# ENERGIS_DispBrd_Rack-PDU_1_1_0.net
KiCad netlist of a schematic drawn in EAGLE
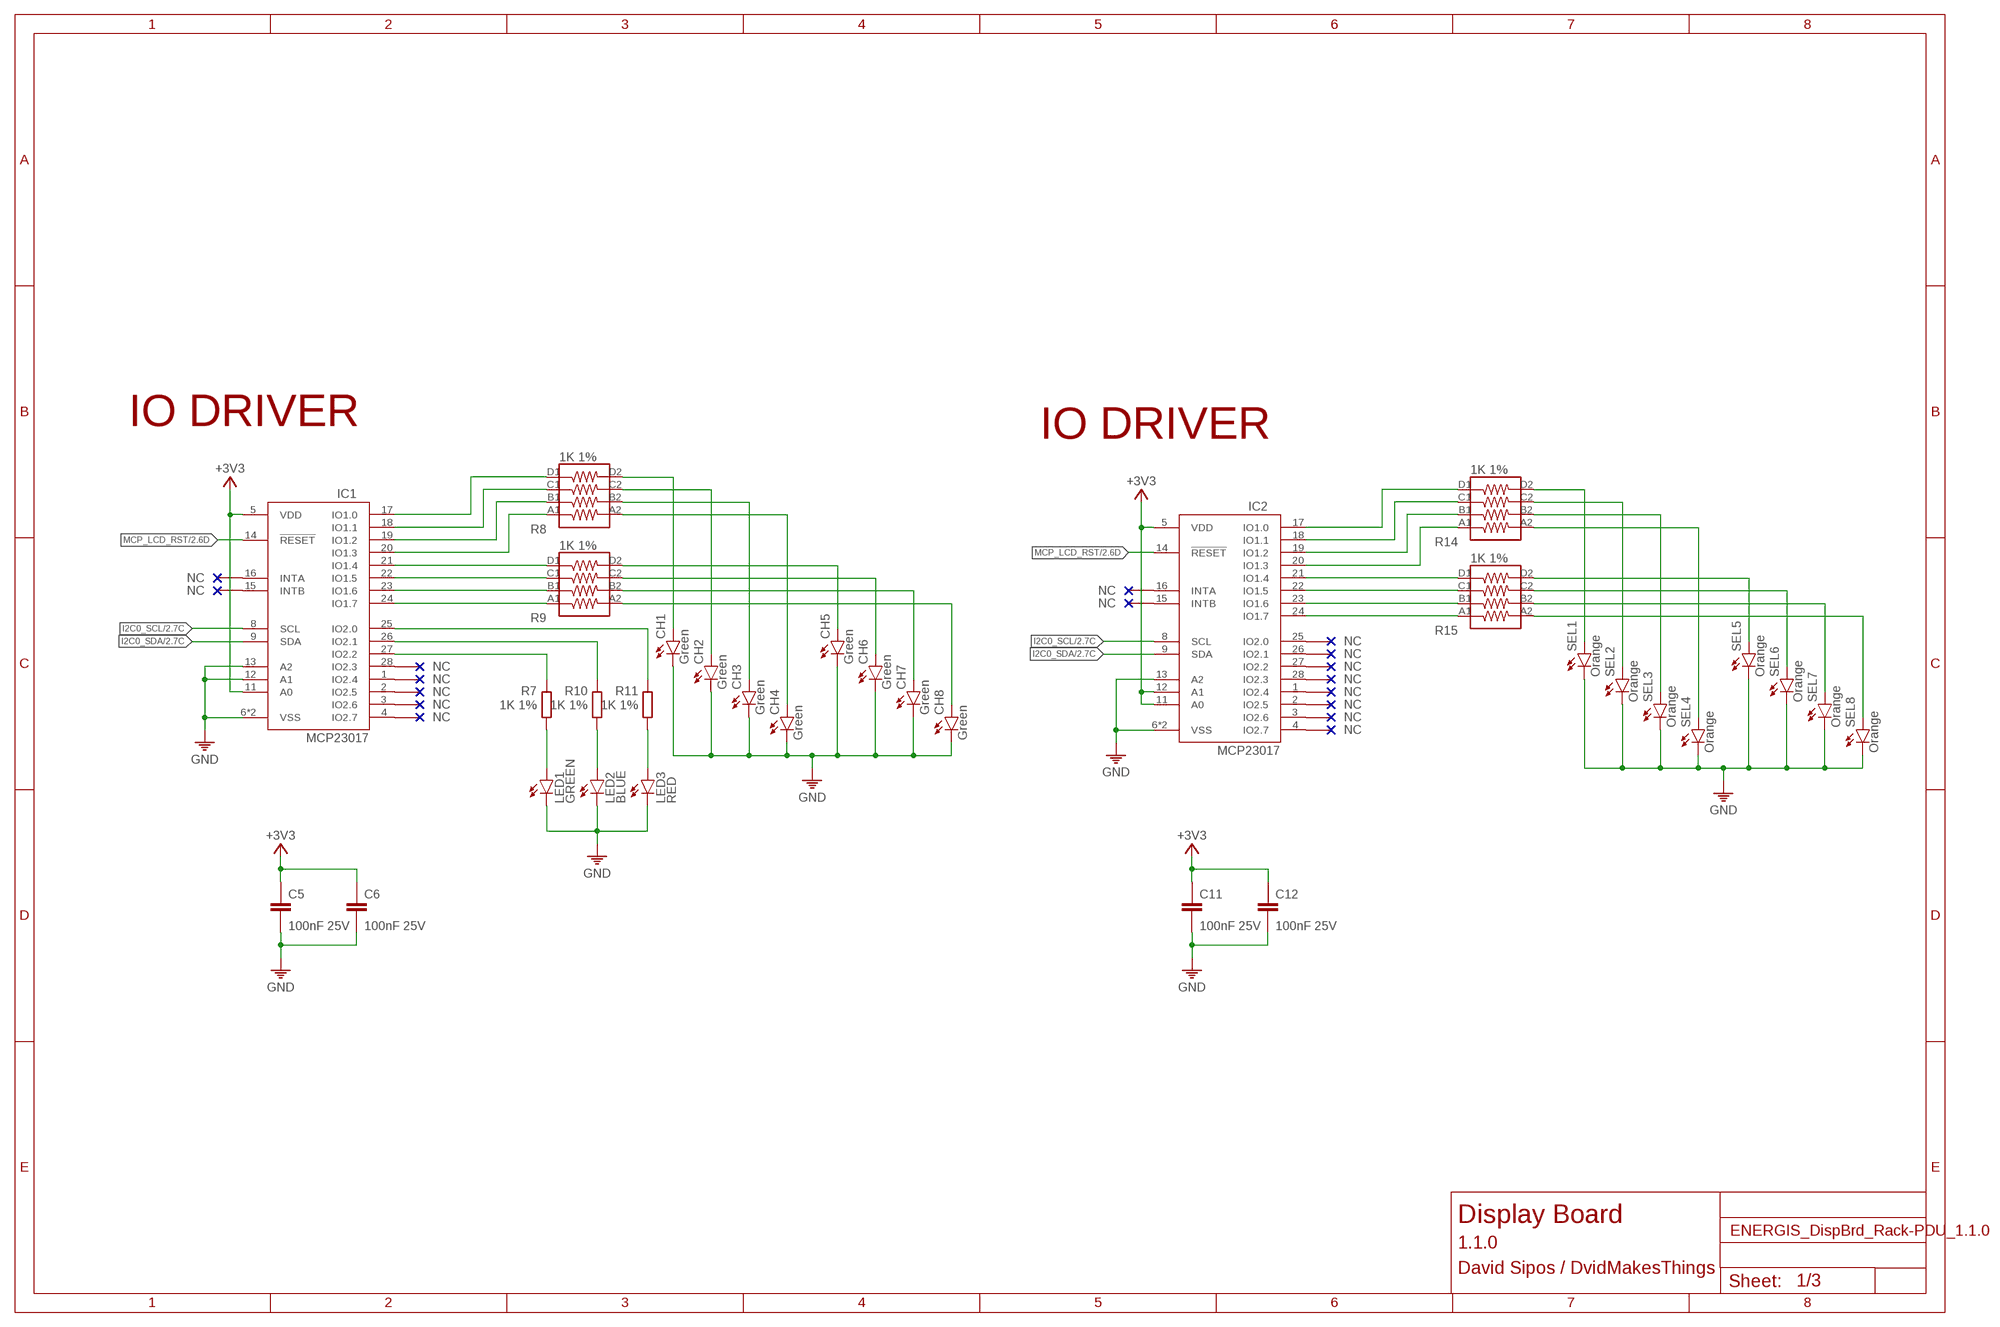
[diagram p0: schematic, sheet 1]
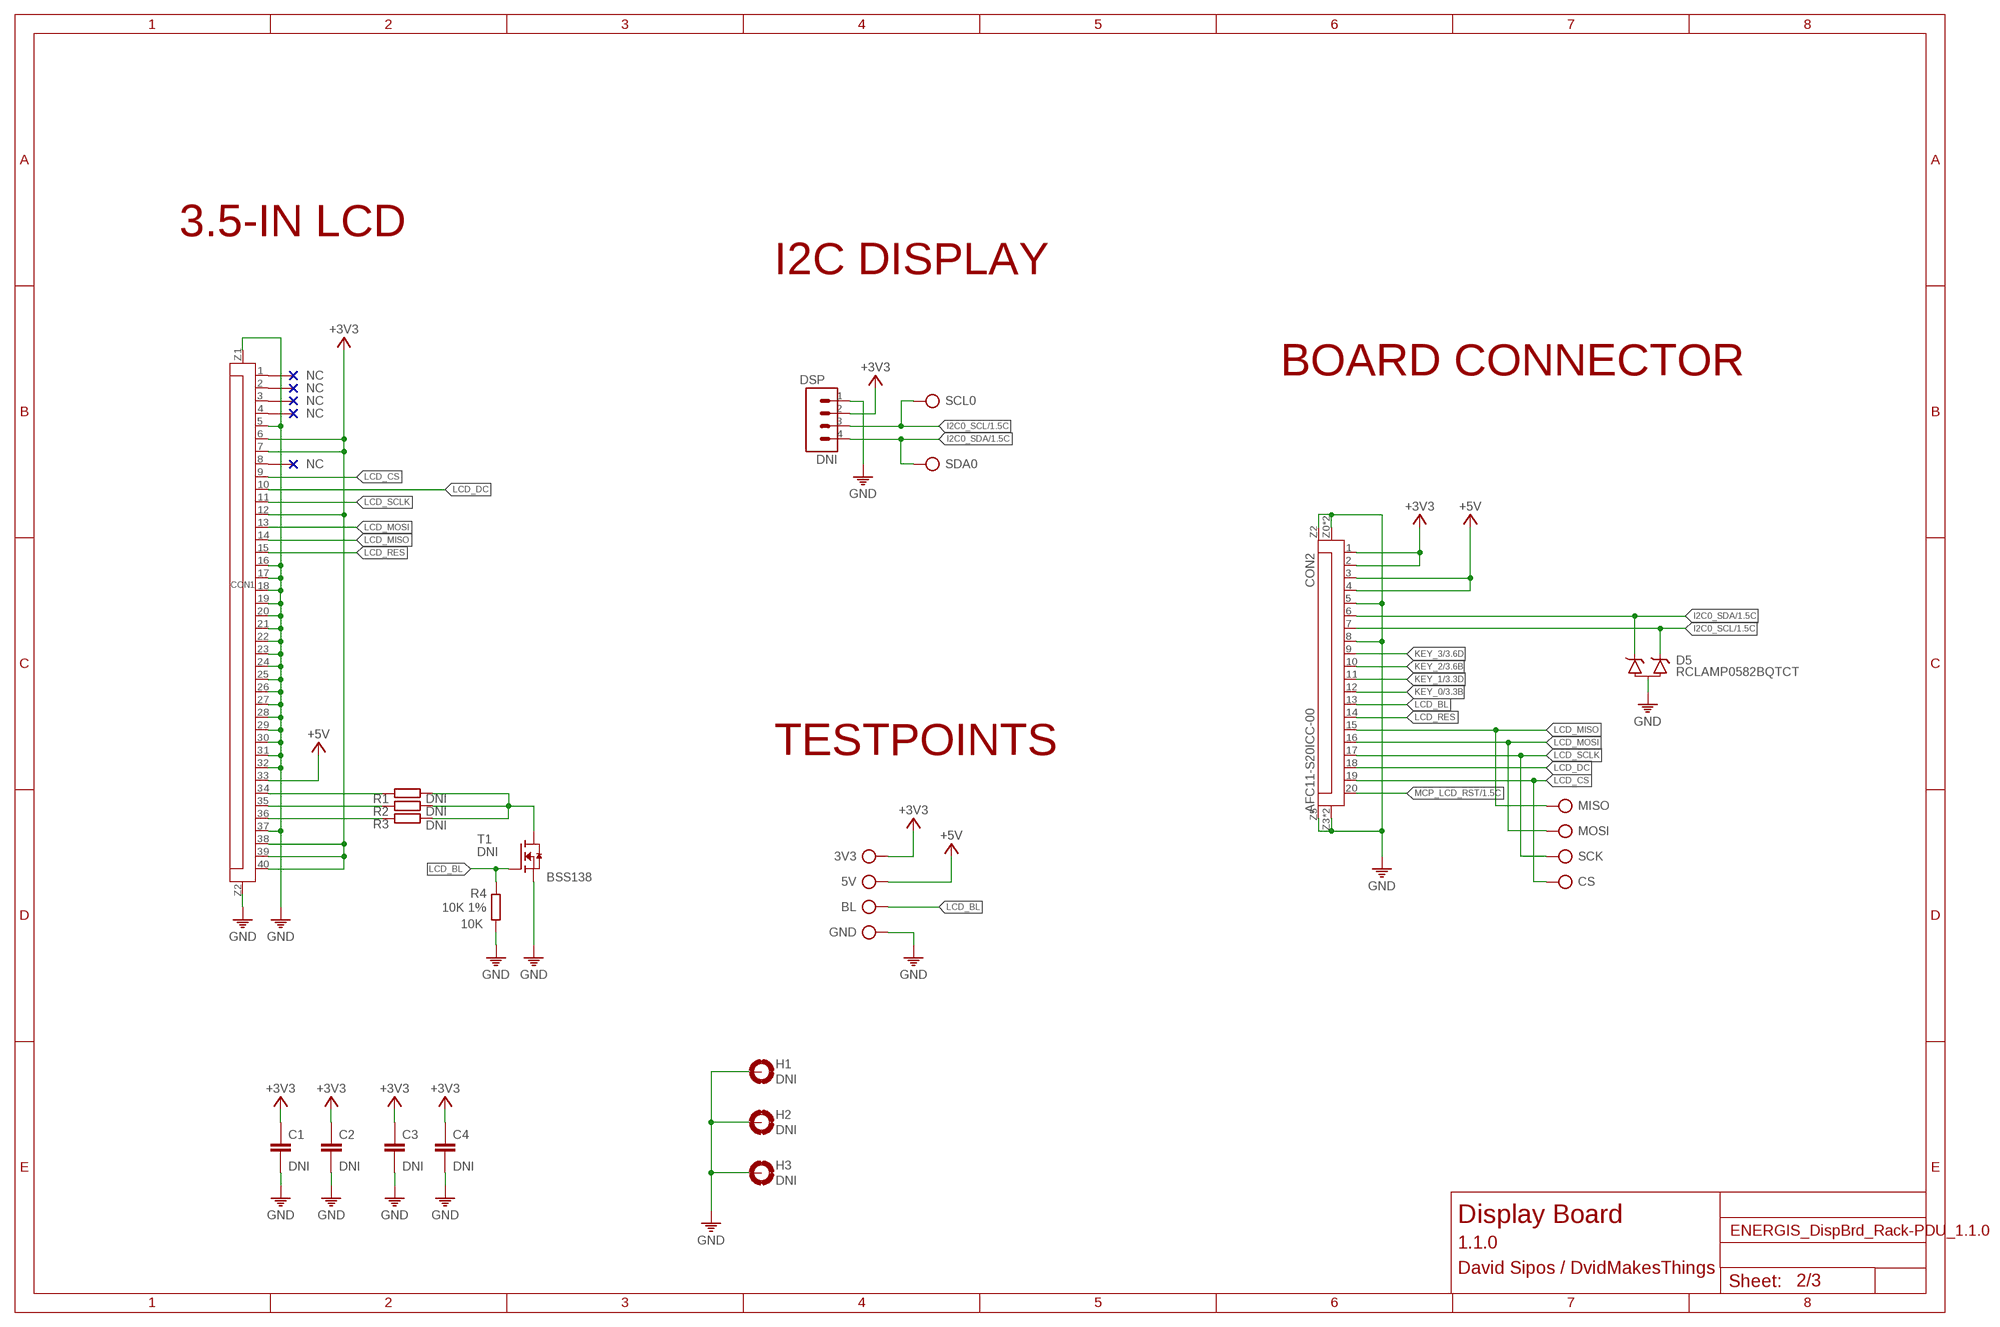
[diagram p1: schematic, sheet 2]
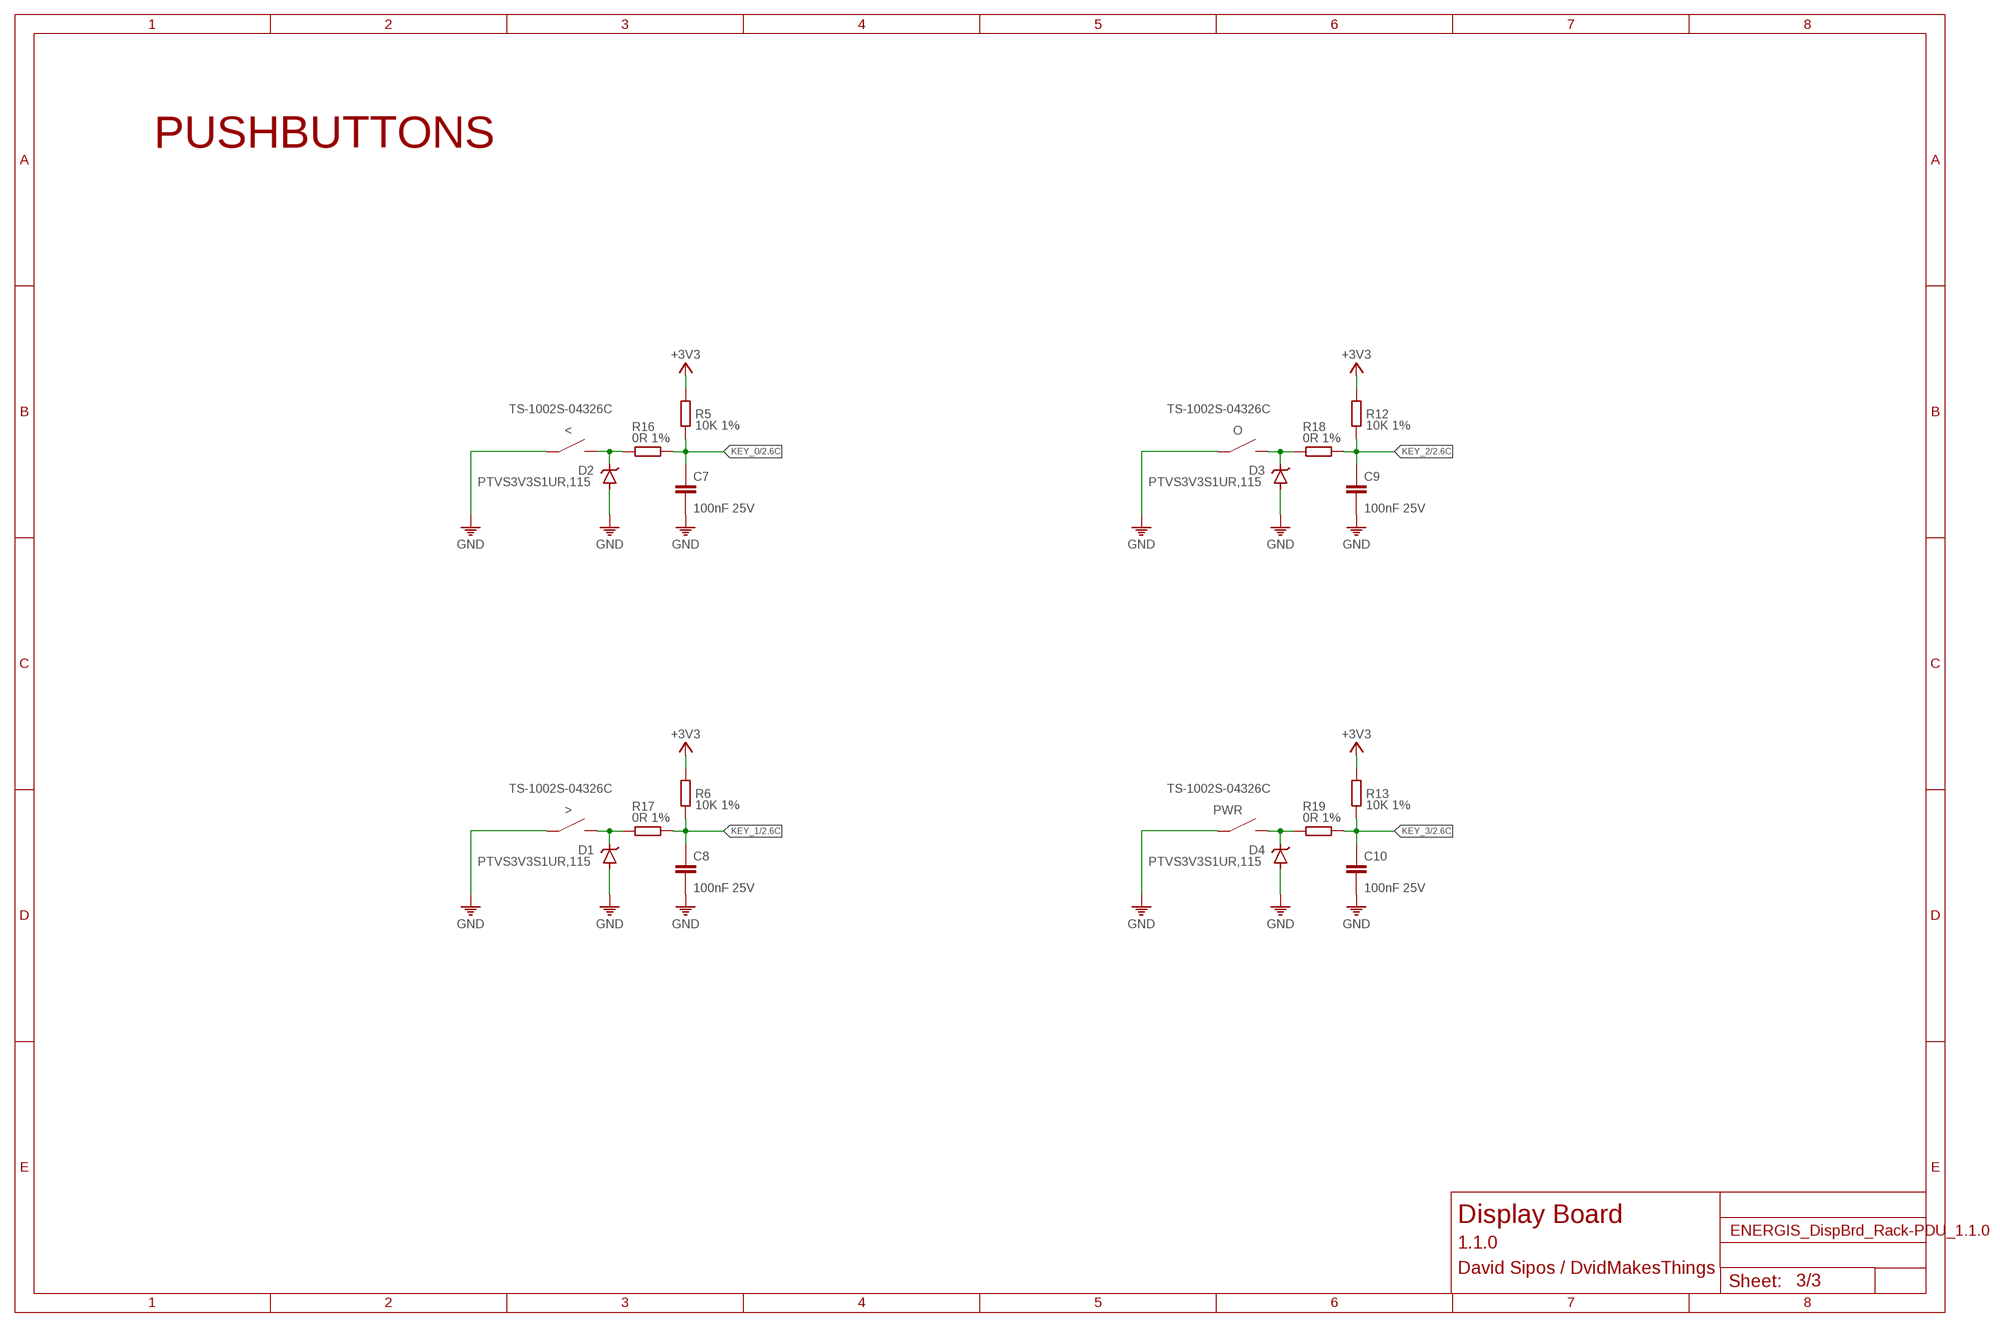
[diagram p2: schematic, sheet 3]

(export (version "E")
  (design (tool "Eeschema 10.0.6"))
  (components
    (comp (ref "<")
      (value "TS-1002S-04326C")
      (footprint "eagle-import:PUSHBUTTON-6X6")
      (fields
        (field (name "HQ_PART") "SW0049370")
        (field (name "LCSC_PART") "C455108")
        (field (name "MANUFACTURER") "USAKRO")
      )
      (libsource (lib "eagle-import") (part "SWITCH6X6-SHORT"))
    )
    (comp (ref ">")
      (value "TS-1002S-04326C")
      (footprint "eagle-import:PUSHBUTTON-6X6")
      (fields
        (field (name "HQ_PART") "SW0049370")
        (field (name "LCSC_PART") "C455108")
        (field (name "MANUFACTURER") "USAKRO")
      )
      (libsource (lib "eagle-import") (part "SWITCH6X6-SHORT"))
    )
    (comp (ref "C7")
      (value "100nF 25V")
      (footprint "eagle-import:0402")
      (fields
        (field (name "HQ_PART") "CA0176807")
        (field (name "LCSC_PART") "C56392")
        (field (name "MANUFACTURER") "Walsin")
      )
      (libsource (lib "eagle-import") (part "100NF-25V-0402"))
    )
    (comp (ref "C8")
      (value "100nF 25V")
      (footprint "eagle-import:0402")
      (fields
        (field (name "HQ_PART") "CA0176807")
        (field (name "LCSC_PART") "C56392")
        (field (name "MANUFACTURER") "Walsin")
      )
      (libsource (lib "eagle-import") (part "100NF-25V-0402"))
    )
    (comp (ref "C9")
      (value "100nF 25V")
      (footprint "eagle-import:0402")
      (fields
        (field (name "HQ_PART") "CA0176807")
        (field (name "LCSC_PART") "C56392")
        (field (name "MANUFACTURER") "Walsin")
      )
      (libsource (lib "eagle-import") (part "100NF-25V-0402"))
    )
    (comp (ref "C10")
      (value "100nF 25V")
      (footprint "eagle-import:0402")
      (fields
        (field (name "HQ_PART") "CA0176807")
        (field (name "LCSC_PART") "C56392")
        (field (name "MANUFACTURER") "Walsin")
      )
      (libsource (lib "eagle-import") (part "100NF-25V-0402"))
    )
    (comp (ref "D1")
      (value "PTVS3V3S1UR,115")
      (footprint "eagle-import:SOD-123")
      (fields
        (field (name "HQ_PART") "CP0009318")
        (field (name "LCSC_PART") "C183521")
        (field (name "MANUFACTURER") "Nexperia")
      )
      (libsource (lib "eagle-import") (part "PTVS3V3S1UR,115"))
    )
    (comp (ref "D2")
      (value "PTVS3V3S1UR,115")
      (footprint "eagle-import:SOD-123")
      (fields
        (field (name "HQ_PART") "CP0009318")
        (field (name "LCSC_PART") "C183521")
        (field (name "MANUFACTURER") "Nexperia")
      )
      (libsource (lib "eagle-import") (part "PTVS3V3S1UR,115"))
    )
    (comp (ref "D3")
      (value "PTVS3V3S1UR,115")
      (footprint "eagle-import:SOD-123")
      (fields
        (field (name "HQ_PART") "CP0009318")
        (field (name "LCSC_PART") "C183521")
        (field (name "MANUFACTURER") "Nexperia")
      )
      (libsource (lib "eagle-import") (part "PTVS3V3S1UR,115"))
    )
    (comp (ref "D4")
      (value "PTVS3V3S1UR,115")
      (footprint "eagle-import:SOD-123")
      (fields
        (field (name "HQ_PART") "CP0009318")
        (field (name "LCSC_PART") "C183521")
        (field (name "MANUFACTURER") "Nexperia")
      )
      (libsource (lib "eagle-import") (part "PTVS3V3S1UR,115"))
    )
    (comp (ref "O")
      (value "TS-1002S-04326C")
      (footprint "eagle-import:PUSHBUTTON-6X6")
      (fields
        (field (name "HQ_PART") "SW0049370")
        (field (name "LCSC_PART") "C455108")
        (field (name "MANUFACTURER") "USAKRO")
      )
      (libsource (lib "eagle-import") (part "SWITCH6X6-SHORT"))
    )
    (comp (ref "PWR")
      (value "TS-1002S-04326C")
      (footprint "eagle-import:PUSHBUTTON-6X6")
      (fields
        (field (name "HQ_PART") "SW0049370")
        (field (name "LCSC_PART") "C455108")
        (field (name "MANUFACTURER") "USAKRO")
      )
      (libsource (lib "eagle-import") (part "SWITCH6X6-SHORT"))
    )
    (comp (ref "R5")
      (value "10K 1%")
      (footprint "eagle-import:0402")
      (fields
        (field (name "HQ_PART") "RE0207399")
        (field (name "LCSC_PART") "C25744")
        (field (name "MANUFACTURER") "ROHM")
      )
      (libsource (lib "eagle-import") (part "10K-1%0402"))
    )
    (comp (ref "R6")
      (value "10K 1%")
      (footprint "eagle-import:0402")
      (fields
        (field (name "HQ_PART") "RE0207399")
        (field (name "LCSC_PART") "C25744")
        (field (name "MANUFACTURER") "ROHM")
      )
      (libsource (lib "eagle-import") (part "10K-1%0402"))
    )
    (comp (ref "R12")
      (value "10K 1%")
      (footprint "eagle-import:0402")
      (fields
        (field (name "HQ_PART") "RE0207399")
        (field (name "LCSC_PART") "C25744")
        (field (name "MANUFACTURER") "ROHM")
      )
      (libsource (lib "eagle-import") (part "10K-1%0402"))
    )
    (comp (ref "R13")
      (value "10K 1%")
      (footprint "eagle-import:0402")
      (fields
        (field (name "HQ_PART") "RE0207399")
        (field (name "LCSC_PART") "C25744")
        (field (name "MANUFACTURER") "ROHM")
      )
      (libsource (lib "eagle-import") (part "10K-1%0402"))
    )
    (comp (ref "R16")
      (value "0R 1%")
      (footprint "eagle-import:0402")
      (fields
        (field (name "HQ_PART") "RE0250181")
        (field (name "LCSC_PART") "C17168")
        (field (name "MANUFACTURER") "YAGEO")
      )
      (libsource (lib "eagle-import") (part "0R0402"))
    )
    (comp (ref "R17")
      (value "0R 1%")
      (footprint "eagle-import:0402")
      (fields
        (field (name "HQ_PART") "RE0250181")
        (field (name "LCSC_PART") "C17168")
        (field (name "MANUFACTURER") "YAGEO")
      )
      (libsource (lib "eagle-import") (part "0R0402"))
    )
    (comp (ref "R18")
      (value "0R 1%")
      (footprint "eagle-import:0402")
      (fields
        (field (name "HQ_PART") "RE0250181")
        (field (name "LCSC_PART") "C17168")
        (field (name "MANUFACTURER") "YAGEO")
      )
      (libsource (lib "eagle-import") (part "0R0402"))
    )
    (comp (ref "R19")
      (value "0R 1%")
      (footprint "eagle-import:0402")
      (fields
        (field (name "HQ_PART") "RE0250181")
        (field (name "LCSC_PART") "C17168")
        (field (name "MANUFACTURER") "YAGEO")
      )
      (libsource (lib "eagle-import") (part "0R0402"))
    )
    (comp (ref "3V3")
      (value "DNI")
      (footprint "eagle-import:TP-ROUND")
      (libsource (lib "eagle-import") (part "TP-ROUND"))
    )
    (comp (ref "5V")
      (value "DNI")
      (footprint "eagle-import:TP-ROUND")
      (libsource (lib "eagle-import") (part "TP-ROUND"))
    )
    (comp (ref "BL")
      (value "DNI")
      (footprint "eagle-import:TP-ROUND")
      (libsource (lib "eagle-import") (part "TP-ROUND"))
    )
    (comp (ref "C1")
      (value "DNI")
      (footprint "eagle-import:C0402")
      (libsource (lib "eagle-import") (part "C-0402"))
    )
    (comp (ref "C2")
      (value "DNI")
      (footprint "eagle-import:C0402")
      (libsource (lib "eagle-import") (part "C-0402"))
    )
    (comp (ref "C3")
      (value "DNI")
      (footprint "eagle-import:C0402")
      (libsource (lib "eagle-import") (part "C-0402"))
    )
    (comp (ref "C4")
      (value "DNI")
      (footprint "eagle-import:C0402")
      (libsource (lib "eagle-import") (part "C-0402"))
    )
    (comp (ref "CON1")
      (value "DNI")
      (footprint "eagle-import:FPC40_3.5TFT")
      (libsource (lib "eagle-import") (part "FPC40-HD"))
    )
    (comp (ref "CON2")
      (value "AFC11-S20ICC-00")
      (footprint "eagle-import:FPC20")
      (fields
        (field (name "HQ_PART") "CO0889517")
        (field (name "LCSC_PART") "C11073")
        (field (name "MANUFACTURER") "JS")
      )
      (libsource (lib "eagle-import") (part "AFC11-S20ICC-00"))
    )
    (comp (ref "CS")
      (value "DNI")
      (footprint "eagle-import:TP-ROUND")
      (libsource (lib "eagle-import") (part "TP-ROUND"))
    )
    (comp (ref "D5")
      (value "RCLAMP0582BQTCT")
      (footprint "eagle-import:SC75")
      (fields
        (field (name "HQ_PART") "PD0007296")
        (field (name "LCSC_PART") "C841193")
        (field (name "MANUFACTURER") "SEMTECH")
      )
      (libsource (lib "eagle-import") (part "RCLAMP0582BQTCT-"))
    )
    (comp (ref "DSP")
      (value "DNI")
      (footprint "eagle-import:1X4")
      (libsource (lib "eagle-import") (part "CON-1X4"))
    )
    (comp (ref "GND")
      (value "DNI")
      (footprint "eagle-import:TP-ROUND")
      (libsource (lib "eagle-import") (part "TP-ROUND"))
    )
    (comp (ref "H1")
      (value "DNI")
      (footprint "eagle-import:3,2-PAD")
      (libsource (lib "eagle-import") (part "MOUNT-PAD-ROUND3.2"))
    )
    (comp (ref "H2")
      (value "DNI")
      (footprint "eagle-import:3,2-PAD")
      (libsource (lib "eagle-import") (part "MOUNT-PAD-ROUND3.2"))
    )
    (comp (ref "H3")
      (value "DNI")
      (footprint "eagle-import:3,2-PAD")
      (libsource (lib "eagle-import") (part "MOUNT-PAD-ROUND3.2"))
    )
    (comp (ref "MISO")
      (value "DNI")
      (footprint "eagle-import:TP-ROUND")
      (libsource (lib "eagle-import") (part "TP-ROUND"))
    )
    (comp (ref "MOSI")
      (value "DNI")
      (footprint "eagle-import:TP-ROUND")
      (libsource (lib "eagle-import") (part "TP-ROUND"))
    )
    (comp (ref "R1")
      (value "DNI")
      (footprint "eagle-import:0402")
      (libsource (lib "eagle-import") (part "R0402"))
    )
    (comp (ref "R2")
      (value "DNI")
      (footprint "eagle-import:0402")
      (libsource (lib "eagle-import") (part "R0402"))
    )
    (comp (ref "R3")
      (value "DNI")
      (footprint "eagle-import:0402")
      (libsource (lib "eagle-import") (part "R0402"))
    )
    (comp (ref "R4")
      (value "10K 1%")
      (footprint "eagle-import:0402")
      (fields
        (field (name "HQ_PART") "RE0207399")
        (field (name "LCSC_PART") "C25744")
        (field (name "MANUFACTURER") "ROHM")
      )
      (libsource (lib "eagle-import") (part "10K-1%0402"))
    )
    (comp (ref "SCK")
      (value "DNI")
      (footprint "eagle-import:TP-ROUND")
      (libsource (lib "eagle-import") (part "TP-ROUND"))
    )
    (comp (ref "SCL0")
      (value "DNI")
      (footprint "eagle-import:TP-ROUND")
      (libsource (lib "eagle-import") (part "TP-ROUND"))
    )
    (comp (ref "SDA0")
      (value "DNI")
      (footprint "eagle-import:TP-ROUND")
      (libsource (lib "eagle-import") (part "TP-ROUND"))
    )
    (comp (ref "T1")
      (value "DNI")
      (footprint "eagle-import:SOT23")
      (fields
        (field (name "HQ_PART") "DS0190318")
        (field (name "MANUFACTURER") "HUASHUO")
        (field (name "MPN") "BSS138")
      )
      (libsource (lib "eagle-import") (part "BSS138"))
    )
    (comp (ref "C5")
      (value "100nF 25V")
      (footprint "eagle-import:0402")
      (fields
        (field (name "HQ_PART") "CA0176807")
        (field (name "LCSC_PART") "C56392")
        (field (name "MANUFACTURER") "Walsin")
      )
      (libsource (lib "eagle-import") (part "100NF-25V-0402"))
    )
    (comp (ref "C6")
      (value "100nF 25V")
      (footprint "eagle-import:0402")
      (fields
        (field (name "HQ_PART") "CA0176807")
        (field (name "LCSC_PART") "C56392")
        (field (name "MANUFACTURER") "Walsin")
      )
      (libsource (lib "eagle-import") (part "100NF-25V-0402"))
    )
    (comp (ref "C11")
      (value "100nF 25V")
      (footprint "eagle-import:0402")
      (fields
        (field (name "HQ_PART") "CA0176807")
        (field (name "LCSC_PART") "C56392")
        (field (name "MANUFACTURER") "Walsin")
      )
      (libsource (lib "eagle-import") (part "100NF-25V-0402"))
    )
    (comp (ref "C12")
      (value "100nF 25V")
      (footprint "eagle-import:0402")
      (fields
        (field (name "HQ_PART") "CA0176807")
        (field (name "LCSC_PART") "C56392")
        (field (name "MANUFACTURER") "Walsin")
      )
      (libsource (lib "eagle-import") (part "100NF-25V-0402"))
    )
    (comp (ref "CH1")
      (value "Green")
      (footprint "eagle-import:LED-0805")
      (fields
        (field (name "HQ_PART") "PH0094653")
        (field (name "LCSC_PART") "C2297")
        (field (name "MANUFACTURER") "MEIHUA")
      )
      (libsource (lib "eagle-import") (part "LED-GREENLED-0805"))
    )
    (comp (ref "CH2")
      (value "Green")
      (footprint "eagle-import:LED-0805")
      (fields
        (field (name "HQ_PART") "PH0094653")
        (field (name "LCSC_PART") "C2297")
        (field (name "MANUFACTURER") "MEIHUA")
      )
      (libsource (lib "eagle-import") (part "LED-GREENLED-0805"))
    )
    (comp (ref "CH3")
      (value "Green")
      (footprint "eagle-import:LED-0805")
      (fields
        (field (name "HQ_PART") "PH0094653")
        (field (name "LCSC_PART") "C2297")
        (field (name "MANUFACTURER") "MEIHUA")
      )
      (libsource (lib "eagle-import") (part "LED-GREENLED-0805"))
    )
    (comp (ref "CH4")
      (value "Green")
      (footprint "eagle-import:LED-0805")
      (fields
        (field (name "HQ_PART") "PH0094653")
        (field (name "LCSC_PART") "C2297")
        (field (name "MANUFACTURER") "MEIHUA")
      )
      (libsource (lib "eagle-import") (part "LED-GREENLED-0805"))
    )
    (comp (ref "CH5")
      (value "Green")
      (footprint "eagle-import:LED-0805")
      (fields
        (field (name "HQ_PART") "PH0094653")
        (field (name "LCSC_PART") "C2297")
        (field (name "MANUFACTURER") "MEIHUA")
      )
      (libsource (lib "eagle-import") (part "LED-GREENLED-0805"))
    )
    (comp (ref "CH6")
      (value "Green")
      (footprint "eagle-import:LED-0805")
      (fields
        (field (name "HQ_PART") "PH0094653")
        (field (name "LCSC_PART") "C2297")
        (field (name "MANUFACTURER") "MEIHUA")
      )
      (libsource (lib "eagle-import") (part "LED-GREENLED-0805"))
    )
    (comp (ref "CH7")
      (value "Green")
      (footprint "eagle-import:LED-0805")
      (fields
        (field (name "HQ_PART") "PH0094653")
        (field (name "LCSC_PART") "C2297")
        (field (name "MANUFACTURER") "MEIHUA")
      )
      (libsource (lib "eagle-import") (part "LED-GREENLED-0805"))
    )
    (comp (ref "CH8")
      (value "Green")
      (footprint "eagle-import:LED-0805")
      (fields
        (field (name "HQ_PART") "PH0094653")
        (field (name "LCSC_PART") "C2297")
        (field (name "MANUFACTURER") "MEIHUA")
      )
      (libsource (lib "eagle-import") (part "LED-GREENLED-0805"))
    )
    (comp (ref "IC1")
      (value "MCP23017T-E/ML")
      (footprint "eagle-import:QFN28[6X6]ML")
      (fields
        (field (name "HQ_PART") "IC0080215")
        (field (name "LCSC_PART") "C629439")
        (field (name "MANUFACTURER") "MICROCHIP")
      )
      (libsource (lib "eagle-import") (part "MCP23017-E/ML"))
    )
    (comp (ref "IC2")
      (value "MCP23017T-E/ML")
      (footprint "eagle-import:QFN28[6X6]ML")
      (fields
        (field (name "HQ_PART") "IC0080215")
        (field (name "LCSC_PART") "C629439")
        (field (name "MANUFACTURER") "MICROCHIP")
      )
      (libsource (lib "eagle-import") (part "MCP23017-E/ML"))
    )
    (comp (ref "LED1")
      (value "GREEN")
      (footprint "eagle-import:LED3MM")
      (fields
        (field (name "HQ_PART") "PH0094890")
        (field (name "LCSC_PART") "C414645")
        (field (name "MANUFACTURER") "MEIHUA")
      )
      (libsource (lib "eagle-import") (part "LED-GREEN3MM-CLEAR"))
    )
    (comp (ref "LED2")
      (value "BLUE")
      (footprint "eagle-import:LED3MM")
      (fields
        (field (name "HQ_PART") "PH0094706")
        (field (name "LCSC_PART") "C86881")
        (field (name "MANUFACTURER") "MEIHUA")
      )
      (libsource (lib "eagle-import") (part "LED-BLUE3MM-CLEAR"))
    )
    (comp (ref "LED3")
      (value "RED")
      (footprint "eagle-import:LED3MM")
      (fields
        (field (name "HQ_PART") "PH0094690")
        (field (name "LCSC_PART") "C330752")
        (field (name "MANUFACTURER") "MEIHUA")
      )
      (libsource (lib "eagle-import") (part "LED-RED3MM-CLEAR"))
    )
    (comp (ref "R7")
      (value "1K 1%")
      (footprint "eagle-import:0402")
      (fields
        (field (name "HQ_PART") "RE0208724")
        (field (name "LCSC_PART") "C11702")
        (field (name "MANUFACTURER") "FH")
      )
      (libsource (lib "eagle-import") (part "1K-1%0402"))
    )
    (comp (ref "R8")
      (value "1K 1%")
      (footprint "eagle-import:_0603X4-1206")
      (fields
        (field (name "HQ_PART") "RE0022532")
        (field (name "LCSC_PART") "C110021")
        (field (name "MANUFACTURER") "Yageo")
      )
      (libsource (lib "eagle-import") (part "1K-1%_ARRAY0603X4-1206"))
    )
    (comp (ref "R9")
      (value "1K 1%")
      (footprint "eagle-import:_0603X4-1206")
      (fields
        (field (name "HQ_PART") "RE0022532")
        (field (name "LCSC_PART") "C110021")
        (field (name "MANUFACTURER") "Yageo")
      )
      (libsource (lib "eagle-import") (part "1K-1%_ARRAY0603X4-1206"))
    )
    (comp (ref "R10")
      (value "1K 1%")
      (footprint "eagle-import:0402")
      (fields
        (field (name "HQ_PART") "RE0208724")
        (field (name "LCSC_PART") "C11702")
        (field (name "MANUFACTURER") "FH")
      )
      (libsource (lib "eagle-import") (part "1K-1%0402"))
    )
    (comp (ref "R11")
      (value "1K 1%")
      (footprint "eagle-import:0402")
      (fields
        (field (name "HQ_PART") "RE0208724")
        (field (name "LCSC_PART") "C11702")
        (field (name "MANUFACTURER") "FH")
      )
      (libsource (lib "eagle-import") (part "1K-1%0402"))
    )
    (comp (ref "R14")
      (value "1K 1%")
      (footprint "eagle-import:_0603X4-1206")
      (fields
        (field (name "HQ_PART") "RE0022532")
        (field (name "LCSC_PART") "C110021")
        (field (name "MANUFACTURER") "Yageo")
      )
      (libsource (lib "eagle-import") (part "1K-1%_ARRAY0603X4-1206"))
    )
    (comp (ref "R15")
      (value "1K 1%")
      (footprint "eagle-import:_0603X4-1206")
      (fields
        (field (name "HQ_PART") "RE0022532")
        (field (name "LCSC_PART") "C110021")
        (field (name "MANUFACTURER") "Yageo")
      )
      (libsource (lib "eagle-import") (part "1K-1%_ARRAY0603X4-1206"))
    )
    (comp (ref "SEL1")
      (value "Orange")
      (footprint "eagle-import:LED-0805")
      (fields
        (field (name "HQ_PART") "PH0093712")
        (field (name "LCSC_PART") "C434437")
        (field (name "MANUFACTURER") "NATIONSTAR")
      )
      (libsource (lib "eagle-import") (part "LED-ORANGELED-0805"))
    )
    (comp (ref "SEL2")
      (value "Orange")
      (footprint "eagle-import:LED-0805")
      (fields
        (field (name "HQ_PART") "PH0093712")
        (field (name "LCSC_PART") "C434437")
        (field (name "MANUFACTURER") "NATIONSTAR")
      )
      (libsource (lib "eagle-import") (part "LED-ORANGELED-0805"))
    )
    (comp (ref "SEL3")
      (value "Orange")
      (footprint "eagle-import:LED-0805")
      (fields
        (field (name "HQ_PART") "PH0093712")
        (field (name "LCSC_PART") "C434437")
        (field (name "MANUFACTURER") "NATIONSTAR")
      )
      (libsource (lib "eagle-import") (part "LED-ORANGELED-0805"))
    )
    (comp (ref "SEL4")
      (value "Orange")
      (footprint "eagle-import:LED-0805")
      (fields
        (field (name "HQ_PART") "PH0093712")
        (field (name "LCSC_PART") "C434437")
        (field (name "MANUFACTURER") "NATIONSTAR")
      )
      (libsource (lib "eagle-import") (part "LED-ORANGELED-0805"))
    )
    (comp (ref "SEL5")
      (value "Orange")
      (footprint "eagle-import:LED-0805")
      (fields
        (field (name "HQ_PART") "PH0093712")
        (field (name "LCSC_PART") "C434437")
        (field (name "MANUFACTURER") "NATIONSTAR")
      )
      (libsource (lib "eagle-import") (part "LED-ORANGELED-0805"))
    )
    (comp (ref "SEL6")
      (value "Orange")
      (footprint "eagle-import:LED-0805")
      (fields
        (field (name "HQ_PART") "PH0093712")
        (field (name "LCSC_PART") "C434437")
        (field (name "MANUFACTURER") "NATIONSTAR")
      )
      (libsource (lib "eagle-import") (part "LED-ORANGELED-0805"))
    )
    (comp (ref "SEL7")
      (value "Orange")
      (footprint "eagle-import:LED-0805")
      (fields
        (field (name "HQ_PART") "PH0093712")
        (field (name "LCSC_PART") "C434437")
        (field (name "MANUFACTURER") "NATIONSTAR")
      )
      (libsource (lib "eagle-import") (part "LED-ORANGELED-0805"))
    )
    (comp (ref "SEL8")
      (value "Orange")
      (footprint "eagle-import:LED-0805")
      (fields
        (field (name "HQ_PART") "PH0093712")
        (field (name "LCSC_PART") "C434437")
        (field (name "MANUFACTURER") "NATIONSTAR")
      )
      (libsource (lib "eagle-import") (part "LED-ORANGELED-0805"))
    )
  )
  (nets
    (net (code "1") (name "+3V3") (class "Default")
      (node (ref "3V3") (pin "TP") (pinfunction "P$1_TP") (pintype "bidirectional"))
      (node (ref "C1") (pin "1") (pinfunction "1_1") (pintype "passive"))
      (node (ref "C11") (pin "1") (pinfunction "1_1") (pintype "passive"))
      (node (ref "C12") (pin "1") (pinfunction "1_1") (pintype "passive"))
      (node (ref "C2") (pin "1") (pinfunction "1_1") (pintype "passive"))
      (node (ref "C3") (pin "1") (pinfunction "1_1") (pintype "passive"))
      (node (ref "C4") (pin "1") (pinfunction "1_1") (pintype "passive"))
      (node (ref "C5") (pin "1") (pinfunction "1_1") (pintype "passive"))
      (node (ref "C6") (pin "1") (pinfunction "1_1") (pintype "passive"))
      (node (ref "CON1") (pin "12") (pinfunction "12_12") (pintype "bidirectional"))
      (node (ref "CON1") (pin "38") (pinfunction "38_38") (pintype "bidirectional"))
      (node (ref "CON1") (pin "39") (pinfunction "39_39") (pintype "bidirectional"))
      (node (ref "CON1") (pin "40") (pinfunction "40_40") (pintype "bidirectional"))
      (node (ref "CON1") (pin "6") (pinfunction "6_6") (pintype "bidirectional"))
      (node (ref "CON1") (pin "7") (pinfunction "7_7") (pintype "bidirectional"))
      (node (ref "CON2") (pin "1") (pinfunction "1_1") (pintype "bidirectional"))
      (node (ref "CON2") (pin "2") (pinfunction "2_2") (pintype "bidirectional"))
      (node (ref "DSP") (pin "2") (pinfunction "P$2_2") (pintype "bidirectional"))
      (node (ref "IC1") (pin "11") (pinfunction "A0_11") (pintype "bidirectional"))
      (node (ref "IC1") (pin "5") (pinfunction "VDD_5") (pintype "bidirectional"))
      (node (ref "IC2") (pin "11") (pinfunction "A0_11") (pintype "bidirectional"))
      (node (ref "IC2") (pin "12") (pinfunction "A1_12") (pintype "bidirectional"))
      (node (ref "IC2") (pin "5") (pinfunction "VDD_5") (pintype "bidirectional"))
      (node (ref "R12") (pin "1") (pinfunction "1_1") (pintype "passive"))
      (node (ref "R13") (pin "1") (pinfunction "1_1") (pintype "passive"))
      (node (ref "R5") (pin "1") (pinfunction "1_1") (pintype "passive"))
      (node (ref "R6") (pin "1") (pinfunction "1_1") (pintype "passive"))
    )
    (net (code "2") (name "+5V") (class "Default")
      (node (ref "5V") (pin "TP") (pinfunction "P$1_TP") (pintype "bidirectional"))
      (node (ref "CON1") (pin "33") (pinfunction "33_33") (pintype "bidirectional"))
      (node (ref "CON2") (pin "3") (pinfunction "3_3") (pintype "bidirectional"))
      (node (ref "CON2") (pin "4") (pinfunction "4_4") (pintype "bidirectional"))
    )
    (net (code "3") (name "GND") (class "Default")
      (node (ref "<") (pin "1") (pinfunction "P$1_1") (pintype "bidirectional"))
      (node (ref "<") (pin "2") (pinfunction "P$1_2") (pintype "bidirectional"))
      (node (ref ">") (pin "1") (pinfunction "P$1_1") (pintype "bidirectional"))
      (node (ref ">") (pin "2") (pinfunction "P$1_2") (pintype "bidirectional"))
      (node (ref "C1") (pin "2") (pinfunction "2_2") (pintype "passive"))
      (node (ref "C10") (pin "2") (pinfunction "2_2") (pintype "passive"))
      (node (ref "C11") (pin "2") (pinfunction "2_2") (pintype "passive"))
      (node (ref "C12") (pin "2") (pinfunction "2_2") (pintype "passive"))
      (node (ref "C2") (pin "2") (pinfunction "2_2") (pintype "passive"))
      (node (ref "C3") (pin "2") (pinfunction "2_2") (pintype "passive"))
      (node (ref "C4") (pin "2") (pinfunction "2_2") (pintype "passive"))
      (node (ref "C5") (pin "2") (pinfunction "2_2") (pintype "passive"))
      (node (ref "C6") (pin "2") (pinfunction "2_2") (pintype "passive"))
      (node (ref "C7") (pin "2") (pinfunction "2_2") (pintype "passive"))
      (node (ref "C8") (pin "2") (pinfunction "2_2") (pintype "passive"))
      (node (ref "C9") (pin "2") (pinfunction "2_2") (pintype "passive"))
      (node (ref "CH1") (pin "C") (pinfunction "C_C") (pintype "passive"))
      (node (ref "CH2") (pin "C") (pinfunction "C_C") (pintype "passive"))
      (node (ref "CH3") (pin "C") (pinfunction "C_C") (pintype "passive"))
      (node (ref "CH4") (pin "C") (pinfunction "C_C") (pintype "passive"))
      (node (ref "CH5") (pin "C") (pinfunction "C_C") (pintype "passive"))
      (node (ref "CH6") (pin "C") (pinfunction "C_C") (pintype "passive"))
      (node (ref "CH7") (pin "C") (pinfunction "C_C") (pintype "passive"))
      (node (ref "CH8") (pin "C") (pinfunction "C_C") (pintype "passive"))
      (node (ref "CON1") (pin "16") (pinfunction "16_16") (pintype "bidirectional"))
      (node (ref "CON1") (pin "17") (pinfunction "17_17") (pintype "bidirectional"))
      (node (ref "CON1") (pin "18") (pinfunction "18_18") (pintype "bidirectional"))
      (node (ref "CON1") (pin "19") (pinfunction "19_19") (pintype "bidirectional"))
      (node (ref "CON1") (pin "20") (pinfunction "20_20") (pintype "bidirectional"))
      (node (ref "CON1") (pin "21") (pinfunction "21_21") (pintype "bidirectional"))
      (node (ref "CON1") (pin "22") (pinfunction "22_22") (pintype "bidirectional"))
      (node (ref "CON1") (pin "23") (pinfunction "23_23") (pintype "bidirectional"))
      (node (ref "CON1") (pin "24") (pinfunction "24_24") (pintype "bidirectional"))
      (node (ref "CON1") (pin "25") (pinfunction "25_25") (pintype "bidirectional"))
      (node (ref "CON1") (pin "26") (pinfunction "26_26") (pintype "bidirectional"))
      (node (ref "CON1") (pin "27") (pinfunction "27_27") (pintype "bidirectional"))
      (node (ref "CON1") (pin "28") (pinfunction "28_28") (pintype "bidirectional"))
      (node (ref "CON1") (pin "29") (pinfunction "29_29") (pintype "bidirectional"))
      (node (ref "CON1") (pin "30") (pinfunction "30_30") (pintype "bidirectional"))
      (node (ref "CON1") (pin "31") (pinfunction "31_31") (pintype "bidirectional"))
      (node (ref "CON1") (pin "32") (pinfunction "32_32") (pintype "bidirectional"))
      (node (ref "CON1") (pin "37") (pinfunction "37_37") (pintype "bidirectional"))
      (node (ref "CON1") (pin "5") (pinfunction "5_5") (pintype "bidirectional"))
      (node (ref "CON1") (pin "Z1") (pinfunction "Z1_Z1") (pintype "bidirectional"))
      (node (ref "CON1") (pin "Z2") (pinfunction "Z2_Z2") (pintype "bidirectional"))
      (node (ref "CON2") (pin "5") (pinfunction "5_5") (pintype "bidirectional"))
      (node (ref "CON2") (pin "8") (pinfunction "8_8") (pintype "bidirectional"))
      (node (ref "CON2") (pin "Z0") (pinfunction "Z1_Z0") (pintype "bidirectional"))
      (node (ref "CON2") (pin "Z1") (pinfunction "Z1_Z1") (pintype "bidirectional"))
      (node (ref "CON2") (pin "Z2") (pinfunction "Z2_Z2") (pintype "bidirectional"))
      (node (ref "CON2") (pin "Z3") (pinfunction "Z3_Z3") (pintype "bidirectional"))
      (node (ref "CON2") (pin "Z4") (pinfunction "Z3_Z4") (pintype "bidirectional"))
      (node (ref "CON2") (pin "Z5") (pinfunction "Z4_Z5") (pintype "bidirectional"))
      (node (ref "D1") (pin "A") (pinfunction "A_A") (pintype "passive"))
      (node (ref "D2") (pin "A") (pinfunction "A_A") (pintype "passive"))
      (node (ref "D3") (pin "A") (pinfunction "A_A") (pintype "passive"))
      (node (ref "D4") (pin "A") (pinfunction "A_A") (pintype "passive"))
      (node (ref "D5") (pin "3") (pinfunction "3_3") (pintype "bidirectional"))
      (node (ref "DSP") (pin "1") (pinfunction "P$1_1") (pintype "bidirectional"))
      (node (ref "GND") (pin "TP") (pinfunction "P$1_TP") (pintype "bidirectional"))
      (node (ref "H1") (pin "B3,2") (pinfunction "MOUNT_B3,2") (pintype "passive"))
      (node (ref "H2") (pin "B3,2") (pinfunction "MOUNT_B3,2") (pintype "passive"))
      (node (ref "H3") (pin "B3,2") (pinfunction "MOUNT_B3,2") (pintype "passive"))
      (node (ref "IC1") (pin "12") (pinfunction "A1_12") (pintype "bidirectional"))
      (node (ref "IC1") (pin "13") (pinfunction "A2_13") (pintype "bidirectional"))
      (node (ref "IC1") (pin "6") (pinfunction "VSS_6") (pintype "bidirectional"))
      (node (ref "IC1") (pin "PAD") (pinfunction "VSS_PAD") (pintype "bidirectional"))
      (node (ref "IC2") (pin "13") (pinfunction "A2_13") (pintype "bidirectional"))
      (node (ref "IC2") (pin "6") (pinfunction "VSS_6") (pintype "bidirectional"))
      (node (ref "IC2") (pin "PAD") (pinfunction "VSS_PAD") (pintype "bidirectional"))
      (node (ref "LED1") (pin "K") (pinfunction "C_K") (pintype "passive"))
      (node (ref "LED2") (pin "K") (pinfunction "C_K") (pintype "passive"))
      (node (ref "LED3") (pin "K") (pinfunction "C_K") (pintype "passive"))
      (node (ref "O") (pin "1") (pinfunction "P$1_1") (pintype "bidirectional"))
      (node (ref "O") (pin "2") (pinfunction "P$1_2") (pintype "bidirectional"))
      (node (ref "PWR") (pin "1") (pinfunction "P$1_1") (pintype "bidirectional"))
      (node (ref "PWR") (pin "2") (pinfunction "P$1_2") (pintype "bidirectional"))
      (node (ref "R4") (pin "2") (pinfunction "2_2") (pintype "passive"))
      (node (ref "SEL1") (pin "C") (pinfunction "C_C") (pintype "passive"))
      (node (ref "SEL2") (pin "C") (pinfunction "C_C") (pintype "passive"))
      (node (ref "SEL3") (pin "C") (pinfunction "C_C") (pintype "passive"))
      (node (ref "SEL4") (pin "C") (pinfunction "C_C") (pintype "passive"))
      (node (ref "SEL5") (pin "C") (pinfunction "C_C") (pintype "passive"))
      (node (ref "SEL6") (pin "C") (pinfunction "C_C") (pintype "passive"))
      (node (ref "SEL7") (pin "C") (pinfunction "C_C") (pintype "passive"))
      (node (ref "SEL8") (pin "C") (pinfunction "C_C") (pintype "passive"))
      (node (ref "T1") (pin "2") (pinfunction "S_2") (pintype "passive"))
    )
    (net (code "4") (name "I2C0_SCL") (class "Default")
      (node (ref "CON2") (pin "7") (pinfunction "7_7") (pintype "bidirectional"))
      (node (ref "D5") (pin "1") (pinfunction "1_1") (pintype "bidirectional"))
      (node (ref "DSP") (pin "3") (pinfunction "P$3_3") (pintype "bidirectional"))
      (node (ref "IC1") (pin "8") (pinfunction "SCL_8") (pintype "bidirectional"))
      (node (ref "IC2") (pin "8") (pinfunction "SCL_8") (pintype "bidirectional"))
      (node (ref "SCL0") (pin "TP") (pinfunction "P$1_TP") (pintype "bidirectional"))
    )
    (net (code "5") (name "I2C0_SDA") (class "Default")
      (node (ref "CON2") (pin "6") (pinfunction "6_6") (pintype "bidirectional"))
      (node (ref "D5") (pin "2") (pinfunction "2_2") (pintype "bidirectional"))
      (node (ref "DSP") (pin "4") (pinfunction "P$4_4") (pintype "bidirectional"))
      (node (ref "IC1") (pin "9") (pinfunction "SDA_9") (pintype "bidirectional"))
      (node (ref "IC2") (pin "9") (pinfunction "SDA_9") (pintype "bidirectional"))
      (node (ref "SDA0") (pin "TP") (pinfunction "P$1_TP") (pintype "bidirectional"))
    )
    (net (code "6") (name "KEY_0") (class "Default")
      (node (ref "C7") (pin "1") (pinfunction "1_1") (pintype "passive"))
      (node (ref "CON2") (pin "12") (pinfunction "12_12") (pintype "bidirectional"))
      (node (ref "R16") (pin "2") (pinfunction "2_2") (pintype "passive"))
      (node (ref "R5") (pin "2") (pinfunction "2_2") (pintype "passive"))
    )
    (net (code "7") (name "KEY_1") (class "Default")
      (node (ref "C8") (pin "1") (pinfunction "1_1") (pintype "passive"))
      (node (ref "CON2") (pin "11") (pinfunction "11_11") (pintype "bidirectional"))
      (node (ref "R17") (pin "2") (pinfunction "2_2") (pintype "passive"))
      (node (ref "R6") (pin "2") (pinfunction "2_2") (pintype "passive"))
    )
    (net (code "8") (name "KEY_2") (class "Default")
      (node (ref "C9") (pin "1") (pinfunction "1_1") (pintype "passive"))
      (node (ref "CON2") (pin "10") (pinfunction "10_10") (pintype "bidirectional"))
      (node (ref "R12") (pin "2") (pinfunction "2_2") (pintype "passive"))
      (node (ref "R18") (pin "2") (pinfunction "2_2") (pintype "passive"))
    )
    (net (code "9") (name "KEY_3") (class "Default")
      (node (ref "C10") (pin "1") (pinfunction "1_1") (pintype "passive"))
      (node (ref "CON2") (pin "9") (pinfunction "9_9") (pintype "bidirectional"))
      (node (ref "R13") (pin "2") (pinfunction "2_2") (pintype "passive"))
      (node (ref "R19") (pin "2") (pinfunction "2_2") (pintype "passive"))
    )
    (net (code "10") (name "LCD_BL") (class "Default")
      (node (ref "BL") (pin "TP") (pinfunction "P$1_TP") (pintype "bidirectional"))
      (node (ref "CON2") (pin "13") (pinfunction "13_13") (pintype "bidirectional"))
      (node (ref "R4") (pin "1") (pinfunction "1_1") (pintype "passive"))
      (node (ref "T1") (pin "1") (pinfunction "G_1") (pintype "passive"))
    )
    (net (code "11") (name "LCD_CS") (class "Default")
      (node (ref "CON1") (pin "9") (pinfunction "9_9") (pintype "bidirectional"))
      (node (ref "CON2") (pin "19") (pinfunction "19_19") (pintype "bidirectional"))
      (node (ref "CS") (pin "TP") (pinfunction "P$1_TP") (pintype "bidirectional"))
    )
    (net (code "12") (name "LCD_DC") (class "Default")
      (node (ref "CON1") (pin "10") (pinfunction "10_10") (pintype "bidirectional"))
      (node (ref "CON2") (pin "18") (pinfunction "18_18") (pintype "bidirectional"))
    )
    (net (code "13") (name "LCD_MISO") (class "Default")
      (node (ref "CON1") (pin "14") (pinfunction "14_14") (pintype "bidirectional"))
      (node (ref "CON2") (pin "15") (pinfunction "15_15") (pintype "bidirectional"))
      (node (ref "MISO") (pin "TP") (pinfunction "P$1_TP") (pintype "bidirectional"))
    )
    (net (code "14") (name "LCD_MOSI") (class "Default")
      (node (ref "CON1") (pin "13") (pinfunction "13_13") (pintype "bidirectional"))
      (node (ref "CON2") (pin "16") (pinfunction "16_16") (pintype "bidirectional"))
      (node (ref "MOSI") (pin "TP") (pinfunction "P$1_TP") (pintype "bidirectional"))
    )
    (net (code "15") (name "LCD_RES") (class "Default")
      (node (ref "CON1") (pin "15") (pinfunction "15_15") (pintype "bidirectional"))
      (node (ref "CON2") (pin "14") (pinfunction "14_14") (pintype "bidirectional"))
    )
    (net (code "16") (name "LCD_SCLK") (class "Default")
      (node (ref "CON1") (pin "11") (pinfunction "11_11") (pintype "bidirectional"))
      (node (ref "CON2") (pin "17") (pinfunction "17_17") (pintype "bidirectional"))
      (node (ref "SCK") (pin "TP") (pinfunction "P$1_TP") (pintype "bidirectional"))
    )
    (net (code "17") (name "MCP_LCD_RST") (class "Default")
      (node (ref "CON2") (pin "20") (pinfunction "20_20") (pintype "bidirectional"))
      (node (ref "IC1") (pin "14") (pinfunction "~{RESET}_14") (pintype "bidirectional"))
      (node (ref "IC2") (pin "14") (pinfunction "~{RESET}_14") (pintype "bidirectional"))
    )
    (net (code "18") (name "Net-(<-P$2-Pad3)") (class "Default")
      (node (ref "<") (pin "3") (pinfunction "P$2_3") (pintype "bidirectional"))
      (node (ref "<") (pin "4") (pinfunction "P$2_4") (pintype "bidirectional"))
      (node (ref "D2") (pin "C") (pinfunction "C_C") (pintype "passive"))
      (node (ref "R16") (pin "1") (pinfunction "1_1") (pintype "passive"))
    )
    (net (code "19") (name "Net-(>-P$2-Pad3)") (class "Default")
      (node (ref ">") (pin "3") (pinfunction "P$2_3") (pintype "bidirectional"))
      (node (ref ">") (pin "4") (pinfunction "P$2_4") (pintype "bidirectional"))
      (node (ref "D1") (pin "C") (pinfunction "C_C") (pintype "passive"))
      (node (ref "R17") (pin "1") (pinfunction "1_1") (pintype "passive"))
    )
    (net (code "20") (name "Net-(CON1-Pad34)") (class "Default")
      (node (ref "CON1") (pin "34") (pinfunction "34_34") (pintype "bidirectional"))
      (node (ref "R1") (pin "2") (pinfunction "2_2") (pintype "passive"))
    )
    (net (code "21") (name "Net-(CON1-Pad35)") (class "Default")
      (node (ref "CON1") (pin "35") (pinfunction "35_35") (pintype "bidirectional"))
      (node (ref "R2") (pin "2") (pinfunction "2_2") (pintype "passive"))
    )
    (net (code "22") (name "Net-(CON1-Pad36)") (class "Default")
      (node (ref "CON1") (pin "36") (pinfunction "36_36") (pintype "bidirectional"))
      (node (ref "R3") (pin "2") (pinfunction "2_2") (pintype "passive"))
    )
    (net (code "23") (name "Net-(D3-PadC)") (class "Default")
      (node (ref "D3") (pin "C") (pinfunction "C_C") (pintype "passive"))
      (node (ref "O") (pin "3") (pinfunction "P$2_3") (pintype "bidirectional"))
      (node (ref "O") (pin "4") (pinfunction "P$2_4") (pintype "bidirectional"))
      (node (ref "R18") (pin "1") (pinfunction "1_1") (pintype "passive"))
    )
    (net (code "24") (name "Net-(D4-PadC)") (class "Default")
      (node (ref "D4") (pin "C") (pinfunction "C_C") (pintype "passive"))
      (node (ref "PWR") (pin "3") (pinfunction "P$2_3") (pintype "bidirectional"))
      (node (ref "PWR") (pin "4") (pinfunction "P$2_4") (pintype "bidirectional"))
      (node (ref "R19") (pin "1") (pinfunction "1_1") (pintype "passive"))
    )
    (net (code "25") (name "Net-(IC1-IO1.0)") (class "Default")
      (node (ref "IC1") (pin "17") (pinfunction "IO1.0_17") (pintype "bidirectional"))
      (node (ref "R8") (pin "D1") (pinfunction "4_D1") (pintype "passive"))
    )
    (net (code "26") (name "Net-(IC1-IO1.1)") (class "Default")
      (node (ref "IC1") (pin "18") (pinfunction "IO1.1_18") (pintype "bidirectional"))
      (node (ref "R8") (pin "C1") (pinfunction "3_C1") (pintype "passive"))
    )
    (net (code "27") (name "Net-(IC1-IO1.2)") (class "Default")
      (node (ref "IC1") (pin "19") (pinfunction "IO1.2_19") (pintype "bidirectional"))
      (node (ref "R8") (pin "B1") (pinfunction "2_B1") (pintype "passive"))
    )
    (net (code "28") (name "Net-(IC1-IO1.3)") (class "Default")
      (node (ref "IC1") (pin "20") (pinfunction "IO1.3_20") (pintype "bidirectional"))
      (node (ref "R8") (pin "A1") (pinfunction "1_A1") (pintype "passive"))
    )
    (net (code "29") (name "Net-(IC1-IO1.4)") (class "Default")
      (node (ref "IC1") (pin "21") (pinfunction "IO1.4_21") (pintype "bidirectional"))
      (node (ref "R9") (pin "D1") (pinfunction "4_D1") (pintype "passive"))
    )
    (net (code "30") (name "Net-(IC1-IO1.5)") (class "Default")
      (node (ref "IC1") (pin "22") (pinfunction "IO1.5_22") (pintype "bidirectional"))
      (node (ref "R9") (pin "C1") (pinfunction "3_C1") (pintype "passive"))
    )
    (net (code "31") (name "Net-(IC1-IO1.6)") (class "Default")
      (node (ref "IC1") (pin "23") (pinfunction "IO1.6_23") (pintype "bidirectional"))
      (node (ref "R9") (pin "B1") (pinfunction "2_B1") (pintype "passive"))
    )
    (net (code "32") (name "Net-(IC1-IO1.7)") (class "Default")
      (node (ref "IC1") (pin "24") (pinfunction "IO1.7_24") (pintype "bidirectional"))
      (node (ref "R9") (pin "A1") (pinfunction "1_A1") (pintype "passive"))
    )
    (net (code "33") (name "Net-(IC1-IO2.0)") (class "Default")
      (node (ref "IC1") (pin "25") (pinfunction "IO2.0_25") (pintype "bidirectional"))
      (node (ref "R11") (pin "1") (pinfunction "1_1") (pintype "passive"))
    )
    (net (code "34") (name "Net-(IC1-IO2.1)") (class "Default")
      (node (ref "IC1") (pin "26") (pinfunction "IO2.1_26") (pintype "bidirectional"))
      (node (ref "R10") (pin "1") (pinfunction "1_1") (pintype "passive"))
    )
    (net (code "35") (name "Net-(IC1-IO2.2)") (class "Default")
      (node (ref "IC1") (pin "27") (pinfunction "IO2.2_27") (pintype "bidirectional"))
      (node (ref "R7") (pin "1") (pinfunction "1_1") (pintype "passive"))
    )
    (net (code "36") (name "Net-(IC2-IO1.0)") (class "Default")
      (node (ref "IC2") (pin "17") (pinfunction "IO1.0_17") (pintype "bidirectional"))
      (node (ref "R14") (pin "D1") (pinfunction "4_D1") (pintype "passive"))
    )
    (net (code "37") (name "Net-(IC2-IO1.1)") (class "Default")
      (node (ref "IC2") (pin "18") (pinfunction "IO1.1_18") (pintype "bidirectional"))
      (node (ref "R14") (pin "C1") (pinfunction "3_C1") (pintype "passive"))
    )
    (net (code "38") (name "Net-(IC2-IO1.2)") (class "Default")
      (node (ref "IC2") (pin "19") (pinfunction "IO1.2_19") (pintype "bidirectional"))
      (node (ref "R14") (pin "B1") (pinfunction "2_B1") (pintype "passive"))
    )
    (net (code "39") (name "Net-(IC2-IO1.3)") (class "Default")
      (node (ref "IC2") (pin "20") (pinfunction "IO1.3_20") (pintype "bidirectional"))
      (node (ref "R14") (pin "A1") (pinfunction "1_A1") (pintype "passive"))
    )
    (net (code "40") (name "Net-(IC2-IO1.4)") (class "Default")
      (node (ref "IC2") (pin "21") (pinfunction "IO1.4_21") (pintype "bidirectional"))
      (node (ref "R15") (pin "D1") (pinfunction "4_D1") (pintype "passive"))
    )
    (net (code "41") (name "Net-(IC2-IO1.5)") (class "Default")
      (node (ref "IC2") (pin "22") (pinfunction "IO1.5_22") (pintype "bidirectional"))
      (node (ref "R15") (pin "C1") (pinfunction "3_C1") (pintype "passive"))
    )
    (net (code "42") (name "Net-(IC2-IO1.6)") (class "Default")
      (node (ref "IC2") (pin "23") (pinfunction "IO1.6_23") (pintype "bidirectional"))
      (node (ref "R15") (pin "B1") (pinfunction "2_B1") (pintype "passive"))
    )
    (net (code "43") (name "Net-(IC2-IO1.7)") (class "Default")
      (node (ref "IC2") (pin "24") (pinfunction "IO1.7_24") (pintype "bidirectional"))
      (node (ref "R15") (pin "A1") (pinfunction "1_A1") (pintype "passive"))
    )
    (net (code "44") (name "Net-(LED1-PadA)") (class "Default")
      (node (ref "LED1") (pin "A") (pinfunction "A_A") (pintype "passive"))
      (node (ref "R7") (pin "2") (pinfunction "2_2") (pintype "passive"))
    )
    (net (code "45") (name "Net-(LED2-PadA)") (class "Default")
      (node (ref "LED2") (pin "A") (pinfunction "A_A") (pintype "passive"))
      (node (ref "R10") (pin "2") (pinfunction "2_2") (pintype "passive"))
    )
    (net (code "46") (name "Net-(LED3-PadA)") (class "Default")
      (node (ref "LED3") (pin "A") (pinfunction "A_A") (pintype "passive"))
      (node (ref "R11") (pin "2") (pinfunction "2_2") (pintype "passive"))
    )
    (net (code "47") (name "Net-(R8-5)") (class "Default")
      (node (ref "CH1") (pin "A") (pinfunction "A_A") (pintype "passive"))
      (node (ref "R8") (pin "D2") (pinfunction "5_D2") (pintype "passive"))
    )
    (net (code "48") (name "Net-(R8-6)") (class "Default")
      (node (ref "CH2") (pin "A") (pinfunction "A_A") (pintype "passive"))
      (node (ref "R8") (pin "C2") (pinfunction "6_C2") (pintype "passive"))
    )
    (net (code "49") (name "Net-(R8-7)") (class "Default")
      (node (ref "CH3") (pin "A") (pinfunction "A_A") (pintype "passive"))
      (node (ref "R8") (pin "B2") (pinfunction "7_B2") (pintype "passive"))
    )
    (net (code "50") (name "Net-(R8-8)") (class "Default")
      (node (ref "CH4") (pin "A") (pinfunction "A_A") (pintype "passive"))
      (node (ref "R8") (pin "A2") (pinfunction "8_A2") (pintype "passive"))
    )
    (net (code "51") (name "Net-(R9-5)") (class "Default")
      (node (ref "CH5") (pin "A") (pinfunction "A_A") (pintype "passive"))
      (node (ref "R9") (pin "D2") (pinfunction "5_D2") (pintype "passive"))
    )
    (net (code "52") (name "Net-(R9-6)") (class "Default")
      (node (ref "CH6") (pin "A") (pinfunction "A_A") (pintype "passive"))
      (node (ref "R9") (pin "C2") (pinfunction "6_C2") (pintype "passive"))
    )
    (net (code "53") (name "Net-(R9-7)") (class "Default")
      (node (ref "CH7") (pin "A") (pinfunction "A_A") (pintype "passive"))
      (node (ref "R9") (pin "B2") (pinfunction "7_B2") (pintype "passive"))
    )
    (net (code "54") (name "Net-(R9-8)") (class "Default")
      (node (ref "CH8") (pin "A") (pinfunction "A_A") (pintype "passive"))
      (node (ref "R9") (pin "A2") (pinfunction "8_A2") (pintype "passive"))
    )
    (net (code "55") (name "Net-(R14-5)") (class "Default")
      (node (ref "R14") (pin "D2") (pinfunction "5_D2") (pintype "passive"))
      (node (ref "SEL1") (pin "A") (pinfunction "A_A") (pintype "passive"))
    )
    (net (code "56") (name "Net-(R14-6)") (class "Default")
      (node (ref "R14") (pin "C2") (pinfunction "6_C2") (pintype "passive"))
      (node (ref "SEL2") (pin "A") (pinfunction "A_A") (pintype "passive"))
    )
    (net (code "57") (name "Net-(R14-7)") (class "Default")
      (node (ref "R14") (pin "B2") (pinfunction "7_B2") (pintype "passive"))
      (node (ref "SEL3") (pin "A") (pinfunction "A_A") (pintype "passive"))
    )
    (net (code "58") (name "Net-(R14-8)") (class "Default")
      (node (ref "R14") (pin "A2") (pinfunction "8_A2") (pintype "passive"))
      (node (ref "SEL4") (pin "A") (pinfunction "A_A") (pintype "passive"))
    )
    (net (code "59") (name "Net-(R15-5)") (class "Default")
      (node (ref "R15") (pin "D2") (pinfunction "5_D2") (pintype "passive"))
      (node (ref "SEL5") (pin "A") (pinfunction "A_A") (pintype "passive"))
    )
    (net (code "60") (name "Net-(R15-6)") (class "Default")
      (node (ref "R15") (pin "C2") (pinfunction "6_C2") (pintype "passive"))
      (node (ref "SEL6") (pin "A") (pinfunction "A_A") (pintype "passive"))
    )
    (net (code "61") (name "Net-(R15-7)") (class "Default")
      (node (ref "R15") (pin "B2") (pinfunction "7_B2") (pintype "passive"))
      (node (ref "SEL7") (pin "A") (pinfunction "A_A") (pintype "passive"))
    )
    (net (code "62") (name "Net-(R15-8)") (class "Default")
      (node (ref "R15") (pin "A2") (pinfunction "8_A2") (pintype "passive"))
      (node (ref "SEL8") (pin "A") (pinfunction "A_A") (pintype "passive"))
    )
    (net (code "63") (name "Net-(T1-D)") (class "Default")
      (node (ref "R1") (pin "1") (pinfunction "1_1") (pintype "passive"))
      (node (ref "R2") (pin "1") (pinfunction "1_1") (pintype "passive"))
      (node (ref "R3") (pin "1") (pinfunction "1_1") (pintype "passive"))
      (node (ref "T1") (pin "3") (pinfunction "D_3") (pintype "passive"))
    )
    (net (code "64") (name "unconnected-(CON1-Pad1)") (class "Default")
      (node (ref "CON1") (pin "1") (pinfunction "1_1") (pintype "bidirectional"))
    )
    (net (code "65") (name "unconnected-(CON1-Pad2)") (class "Default")
      (node (ref "CON1") (pin "2") (pinfunction "2_2") (pintype "bidirectional"))
    )
    (net (code "66") (name "unconnected-(CON1-Pad3)") (class "Default")
      (node (ref "CON1") (pin "3") (pinfunction "3_3") (pintype "bidirectional"))
    )
    (net (code "67") (name "unconnected-(CON1-Pad4)") (class "Default")
      (node (ref "CON1") (pin "4") (pinfunction "4_4") (pintype "bidirectional"))
    )
    (net (code "68") (name "unconnected-(CON1-Pad8)") (class "Default")
      (node (ref "CON1") (pin "8") (pinfunction "8_8") (pintype "bidirectional"))
    )
    (net (code "69") (name "unconnected-(IC1-INTA-Pad16)") (class "Default")
      (node (ref "IC1") (pin "16") (pinfunction "INTA_16") (pintype "bidirectional"))
    )
    (net (code "70") (name "unconnected-(IC1-INTB-Pad15)") (class "Default")
      (node (ref "IC1") (pin "15") (pinfunction "INTB_15") (pintype "bidirectional"))
    )
    (net (code "71") (name "unconnected-(IC1-IO2.3-Pad28)") (class "Default")
      (node (ref "IC1") (pin "28") (pinfunction "IO2.3_28") (pintype "bidirectional"))
    )
    (net (code "72") (name "unconnected-(IC1-IO2.4-Pad1)") (class "Default")
      (node (ref "IC1") (pin "1") (pinfunction "IO2.4_1") (pintype "bidirectional"))
    )
    (net (code "73") (name "unconnected-(IC1-IO2.5-Pad2)") (class "Default")
      (node (ref "IC1") (pin "2") (pinfunction "IO2.5_2") (pintype "bidirectional"))
    )
    (net (code "74") (name "unconnected-(IC1-IO2.6-Pad3)") (class "Default")
      (node (ref "IC1") (pin "3") (pinfunction "IO2.6_3") (pintype "bidirectional"))
    )
    (net (code "75") (name "unconnected-(IC1-IO2.7-Pad4)") (class "Default")
      (node (ref "IC1") (pin "4") (pinfunction "IO2.7_4") (pintype "bidirectional"))
    )
    (net (code "76") (name "unconnected-(IC2-INTA-Pad16)") (class "Default")
      (node (ref "IC2") (pin "16") (pinfunction "INTA_16") (pintype "bidirectional"))
    )
    (net (code "77") (name "unconnected-(IC2-INTB-Pad15)") (class "Default")
      (node (ref "IC2") (pin "15") (pinfunction "INTB_15") (pintype "bidirectional"))
    )
    (net (code "78") (name "unconnected-(IC2-IO2.0-Pad25)") (class "Default")
      (node (ref "IC2") (pin "25") (pinfunction "IO2.0_25") (pintype "bidirectional"))
    )
    (net (code "79") (name "unconnected-(IC2-IO2.1-Pad26)") (class "Default")
      (node (ref "IC2") (pin "26") (pinfunction "IO2.1_26") (pintype "bidirectional"))
    )
    (net (code "80") (name "unconnected-(IC2-IO2.2-Pad27)") (class "Default")
      (node (ref "IC2") (pin "27") (pinfunction "IO2.2_27") (pintype "bidirectional"))
    )
    (net (code "81") (name "unconnected-(IC2-IO2.3-Pad28)") (class "Default")
      (node (ref "IC2") (pin "28") (pinfunction "IO2.3_28") (pintype "bidirectional"))
    )
    (net (code "82") (name "unconnected-(IC2-IO2.4-Pad1)") (class "Default")
      (node (ref "IC2") (pin "1") (pinfunction "IO2.4_1") (pintype "bidirectional"))
    )
    (net (code "83") (name "unconnected-(IC2-IO2.5-Pad2)") (class "Default")
      (node (ref "IC2") (pin "2") (pinfunction "IO2.5_2") (pintype "bidirectional"))
    )
    (net (code "84") (name "unconnected-(IC2-IO2.6-Pad3)") (class "Default")
      (node (ref "IC2") (pin "3") (pinfunction "IO2.6_3") (pintype "bidirectional"))
    )
    (net (code "85") (name "unconnected-(IC2-IO2.7-Pad4)") (class "Default")
      (node (ref "IC2") (pin "4") (pinfunction "IO2.7_4") (pintype "bidirectional"))
    )
  )
)
